# Sheet1.net
KiCad netlist of a schematic drawn in Altium Designer
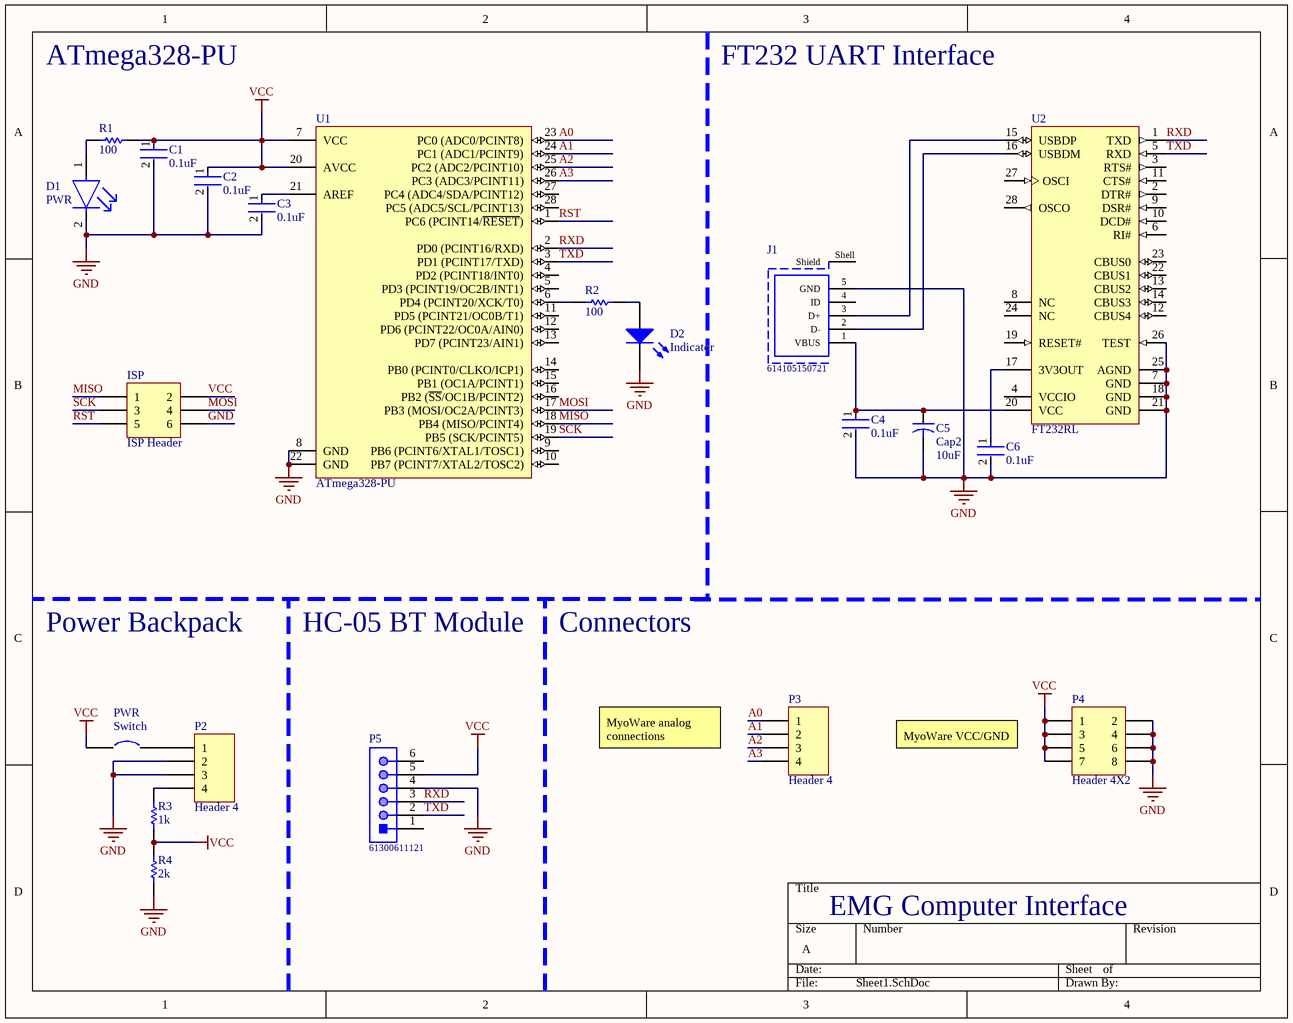
[diagram p0: Sheet1.SchDoc]

(export (version "E")
  (design (tool "Eeschema 10.0.6"))
  (components
    (comp (ref "C1")
      (value "0.1uF")
      (footprint "FP-1206-L_3_2_0_2-W_1_6_0-IPC_C")
      (description "General Purpose Ceramic Capacitor, 1206, 100nF, 5%, X7R, 15%, 100V")
      (fields (field (name "TOLERANCE") "5%") (field (name "VOLTAGE") "100V"))
      (libsource (lib "Altium Content Vault") (part "b4654b650e69147ec39a6b967a45e02"))
    )
    (comp (ref "C2")
      (value "0.1uF")
      (footprint "FP-1206-L_3_2_0_2-W_1_6_0-IPC_C")
      (description "General Purpose Ceramic Capacitor, 1206, 100nF, 5%, X7R, 15%, 100V")
      (fields (field (name "TOLERANCE") "5%") (field (name "VOLTAGE") "100V"))
      (libsource (lib "Altium Content Vault") (part "b4654b650e69147ec39a6b967a45e02"))
    )
    (comp (ref "C3")
      (value "0.1uF")
      (footprint "FP-1206-L_3_2_0_2-W_1_6_0-IPC_C")
      (description "General Purpose Ceramic Capacitor, 1206, 100nF, 5%, X7R, 15%, 100V")
      (fields (field (name "TOLERANCE") "5%") (field (name "VOLTAGE") "100V"))
      (libsource (lib "Altium Content Vault") (part "b4654b650e69147ec39a6b967a45e02"))
    )
    (comp (ref "C4")
      (value "0.1uF")
      (footprint "FP-1206-L_3_2_0_2-W_1_6_0-IPC_C")
      (description "General Purpose Ceramic Capacitor, 1206, 100nF, 5%, X7R, 15%, 100V")
      (fields (field (name "TOLERANCE") "5%") (field (name "VOLTAGE") "100V"))
      (libsource (lib "Altium Content Vault") (part "b4654b650e69147ec39a6b967a45e02"))
    )
    (comp (ref "C5")
      (value "Cap2")
      (footprint "CAPR5-4X5")
      (description "Capacitor")
      (fields (field (name "ALTIUM_VALUE") "10uF") (field (name "PUBLISHER") "Altium Limited"))
      (libsource (lib "Miscellaneous Devices") (part "Cap2"))
    )
    (comp (ref "C6")
      (value "0.1uF")
      (footprint "FP-1206-L_3_2_0_2-W_1_6_0-IPC_C")
      (description "General Purpose Ceramic Capacitor, 1206, 100nF, 5%, X7R, 15%, 100V")
      (fields (field (name "TOLERANCE") "5%") (field (name "VOLTAGE") "100V"))
      (libsource (lib "Altium Content Vault") (part "b4654b650e69147ec39a6b967a45e02"))
    )
    (comp (ref "D1")
      (value "PWR")
      (footprint "FP-SML-LX1206GC-TR-MFG")
      (description "LED GREEN CLEAR 1206 SMD")
      (libsource (lib "Altium Content Vault") (part "ab1c01a81903e929fc6c44469aada92"))
    )
    (comp (ref "D2")
      (value "Indicator")
      (footprint "1206_A")
      (description "SMD mono-color Chip LED, WL-SMCW, Super Red")
      (fields (field (name "MANUFACTURER") "Wuerth Elektronik") (field (name "PARTNUMBER") "150120SS75000"))
      (libsource (lib "Altium Content Vault") (part "WE-LED_K1A2-2"))
    )
    (comp (ref "ISP")
      (value "ISP Header")
      (footprint "HDR2X3")
      (description "Header, 3-Pin, Dual row")
      (fields (field (name "PUBLISHER") "Altium Limited"))
      (libsource (lib "Miscellaneous Connectors") (part "Header 3X2"))
    )
    (comp (ref "J1")
      (value "614105150721")
      (footprint "614105150721")
      (description "Micro USB 2.0 Type B Receptacle WR-COM, Vertical, THT")
      (fields (field (name "MANUFACTURER") "Wurth Elektronik") (field (name "PUBLISHER") "WurthElektronik"))
      (libsource (lib "Altium Content Vault") (part "WE-USB-5-1SHLD"))
    )
    (comp (ref "P2")
      (value "Header 4")
      (footprint "HDR1X4")
      (description "Header, 4-Pin")
      (fields (field (name "PUBLISHER") "Altium Limited"))
      (libsource (lib "Miscellaneous Connectors") (part "Header 4"))
    )
    (comp (ref "P3")
      (value "Header 4")
      (footprint "HDR1X4")
      (description "Header, 4-Pin")
      (fields (field (name "PUBLISHER") "Altium Limited"))
      (libsource (lib "Miscellaneous Connectors") (part "Header 4"))
    )
    (comp (ref "P4")
      (value "Header 4X2")
      (footprint "HDR2X4")
      (description "Header, 4-Pin, Dual row")
      (fields (field (name "PUBLISHER") "Altium Limited"))
      (libsource (lib "Miscellaneous Connectors") (part "Header 4X2"))
    )
    (comp (ref "P5")
      (value "61300611121")
      (footprint "61300611121")
      (description "THT Vertical Pin Header WR-PHD, Pitch 2.54 mm, Single Row, 6 pins")
      (fields (field (name "MANUFACTURER") "Wurth Elektronik") (field (name "PUBLISHER") "WurthElektronik"))
      (libsource (lib "Altium Content Vault") (part "WE-CN-1P-M-R6"))
    )
    (comp (ref "PWR")
      (value "Switch")
      (footprint "SPST-2")
      (description "Circuit Breaker")
      (fields (field (name "PUBLISHER") "Altium Limited"))
      (libsource (lib "Miscellaneous Devices") (part "Circuit Breaker"))
    )
    (comp (ref "R1")
      (value "100")
      (footprint "RESC3216X70X50NL05T20")
      (fields (field (name "MANUFACTURER") "Panasonic") (field (name "PART NUMBER") "ERJ-8ENF1000V"))
      (libsource (lib "Altium Content Vault") (part "RES"))
    )
    (comp (ref "R2")
      (value "100")
      (footprint "RESC3216X70X50NL05T20")
      (fields (field (name "MANUFACTURER") "Panasonic") (field (name "PART NUMBER") "ERJ-8ENF1000V"))
      (libsource (lib "Altium Content Vault") (part "RES"))
    )
    (comp (ref "R3")
      (value "1k")
      (footprint "RESC3216X70X50LL05T20")
      (fields (field (name "MANUFACTURER") "Panasonic") (field (name "PART NUMBER") "ERJ-8ENF1001V"))
      (libsource (lib "Altium Content Vault") (part "RES"))
    )
    (comp (ref "R4")
      (value "2k")
      (footprint "RESC3216X70X50NL05T20")
      (fields (field (name "PART NUMBER") "ERJ-8ENF2001V") (field (name "MANUFACTURER") "Panasonic"))
      (libsource (lib "Altium Content Vault") (part "RES"))
    )
    (comp (ref "U1")
      (value "ATmega328-PU")
      (footprint "28P3")
      (libsource (lib "Altium Content Vault") (part "MC-8B-ATM48-IL28"))
    )
    (comp (ref "U2")
      (value "FT232RL")
      (footprint "FTDI-SSOP-28_M")
      (description "IC USB FS SERIAL UART 28-SSOP")
      (fields (field (name "MANUFACTURER") "FTDI"))
      (libsource (lib "Altium Content Vault") (part "FTDI-FT232-SSOP-28"))
    )
  )
  (nets
    (net (code "1") (name "/A0") (class "Default")
      (node (ref "P3") (pin "1") (pinfunction "1_1") (pintype "passive"))
      (node (ref "U1") (pin "23") (pinfunction "PC0_(ADC0/PCINT8)_23") (pintype "bidirectional"))
    )
    (net (code "2") (name "/A1") (class "Default")
      (node (ref "P3") (pin "2") (pinfunction "2_2") (pintype "passive"))
      (node (ref "U1") (pin "24") (pinfunction "PC1_(ADC1/PCINT9)_24") (pintype "bidirectional"))
    )
    (net (code "3") (name "/A2") (class "Default")
      (node (ref "P3") (pin "3") (pinfunction "3_3") (pintype "passive"))
      (node (ref "U1") (pin "25") (pinfunction "PC2_(ADC2/PCINT10)_25") (pintype "bidirectional"))
    )
    (net (code "4") (name "/A3") (class "Default")
      (node (ref "P3") (pin "4") (pinfunction "4_4") (pintype "passive"))
      (node (ref "U1") (pin "26") (pinfunction "PC3_(ADC3/PCINT11)_26") (pintype "bidirectional"))
    )
    (net (code "5") (name "/MISO") (class "Default")
      (node (ref "ISP") (pin "1") (pinfunction "1_1") (pintype "passive"))
      (node (ref "U1") (pin "18") (pinfunction "PB4_(MISO/PCINT4)_18") (pintype "bidirectional"))
    )
    (net (code "6") (name "/MOSI") (class "Default")
      (node (ref "ISP") (pin "4") (pinfunction "4_4") (pintype "passive"))
      (node (ref "U1") (pin "17") (pinfunction "PB3_(MOSI/OC2A/PCINT3)_17") (pintype "bidirectional"))
    )
    (net (code "7") (name "/RST") (class "Default")
      (node (ref "ISP") (pin "5") (pinfunction "5_5") (pintype "passive"))
      (node (ref "U1") (pin "1") (pinfunction "PC6_(PCINT14/~{RESET})_1") (pintype "bidirectional"))
    )
    (net (code "8") (name "/RXD") (class "Default")
      (node (ref "P5") (pin "3") (pinfunction "3_3") (pintype "passive"))
      (node (ref "U1") (pin "2") (pinfunction "PD0_(PCINT16/RXD)_2") (pintype "bidirectional"))
      (node (ref "U2") (pin "1") (pinfunction "TXD_1") (pintype "output"))
    )
    (net (code "9") (name "/SCK") (class "Default")
      (node (ref "ISP") (pin "3") (pinfunction "3_3") (pintype "passive"))
      (node (ref "U1") (pin "19") (pinfunction "PB5_(SCK/PCINT5)_19") (pintype "bidirectional"))
    )
    (net (code "10") (name "/TXD") (class "Default")
      (node (ref "P5") (pin "2") (pinfunction "2_2") (pintype "passive"))
      (node (ref "U1") (pin "3") (pinfunction "PD1_(PCINT17/TXD)_3") (pintype "bidirectional"))
      (node (ref "U2") (pin "5") (pinfunction "RXD_5") (pintype "input"))
    )
    (net (code "11") (name "GND") (class "Default")
      (node (ref "C1") (pin "2") (pinfunction "2_2") (pintype "passive"))
      (node (ref "C2") (pin "2") (pinfunction "2_2") (pintype "passive"))
      (node (ref "C3") (pin "2") (pinfunction "2_2") (pintype "passive"))
      (node (ref "C4") (pin "2") (pinfunction "2_2") (pintype "passive"))
      (node (ref "C5") (pin "2") (pinfunction "2_2") (pintype "passive"))
      (node (ref "C6") (pin "2") (pinfunction "2_2") (pintype "passive"))
      (node (ref "D1") (pin "2") (pinfunction "C_2") (pintype "passive"))
      (node (ref "D2") (pin "1") (pinfunction "K_1") (pintype "passive"))
      (node (ref "ISP") (pin "6") (pinfunction "6_6") (pintype "passive"))
      (node (ref "J1") (pin "5") (pinfunction "GND_5") (pintype "passive"))
      (node (ref "P2") (pin "2") (pinfunction "2_2") (pintype "passive"))
      (node (ref "P2") (pin "3") (pinfunction "3_3") (pintype "passive"))
      (node (ref "P4") (pin "2") (pinfunction "2_2") (pintype "passive"))
      (node (ref "P4") (pin "4") (pinfunction "4_4") (pintype "passive"))
      (node (ref "P4") (pin "6") (pinfunction "6_6") (pintype "passive"))
      (node (ref "P4") (pin "8") (pinfunction "8_8") (pintype "passive"))
      (node (ref "P5") (pin "4") (pinfunction "4_4") (pintype "passive"))
      (node (ref "R4") (pin "1") (pinfunction "1_1") (pintype "passive"))
      (node (ref "U1") (pin "22") (pinfunction "GND_22") (pintype "power_in"))
      (node (ref "U1") (pin "8") (pinfunction "GND_8") (pintype "power_in"))
      (node (ref "U2") (pin "18") (pinfunction "GND_18") (pintype "power_in"))
      (node (ref "U2") (pin "21") (pinfunction "GND_21") (pintype "power_in"))
      (node (ref "U2") (pin "25") (pinfunction "AGND_25") (pintype "power_in"))
      (node (ref "U2") (pin "26") (pinfunction "TEST_26") (pintype "input"))
      (node (ref "U2") (pin "7") (pinfunction "GND_7") (pintype "power_in"))
    )
    (net (code "12") (name "Net-(D1-A)") (class "Default")
      (node (ref "D1") (pin "1") (pinfunction "A_1") (pintype "passive"))
      (node (ref "R1") (pin "1") (pinfunction "1_1") (pintype "passive"))
    )
    (net (code "13") (name "Net-(D2-A)") (class "Default")
      (node (ref "D2") (pin "2") (pinfunction "A_2") (pintype "passive"))
      (node (ref "R2") (pin "2") (pinfunction "2_2") (pintype "passive"))
    )
    (net (code "14") (name "Net-(J1-D+)") (class "Default")
      (node (ref "J1") (pin "3") (pinfunction "D+_3") (pintype "passive"))
      (node (ref "U2") (pin "15") (pinfunction "USBDP_15") (pintype "bidirectional"))
    )
    (net (code "15") (name "Net-(J1-D-)") (class "Default")
      (node (ref "J1") (pin "2") (pinfunction "D-_2") (pintype "passive"))
      (node (ref "U2") (pin "16") (pinfunction "USBDM_16") (pintype "bidirectional"))
    )
    (net (code "16") (name "Net-(J1-VBUS)") (class "Default")
      (node (ref "C4") (pin "1") (pinfunction "1_1") (pintype "passive"))
      (node (ref "C5") (pin "1") (pinfunction "1_1") (pintype "passive"))
      (node (ref "J1") (pin "1") (pinfunction "VBUS_1") (pintype "passive"))
      (node (ref "U2") (pin "20") (pinfunction "VCC_20") (pintype "power_in"))
    )
    (net (code "17") (name "Net-(P2-Pad1)") (class "Default")
      (node (ref "P2") (pin "1") (pinfunction "1_1") (pintype "passive"))
      (node (ref "PWR") (pin "2") (pinfunction "2_2") (pintype "passive"))
    )
    (net (code "18") (name "Net-(P2-Pad4)") (class "Default")
      (node (ref "P2") (pin "4") (pinfunction "4_4") (pintype "passive"))
      (node (ref "R3") (pin "2") (pinfunction "2_2") (pintype "passive"))
    )
    (net (code "19") (name "Net-(U1-AREF)") (class "Default")
      (node (ref "C3") (pin "1") (pinfunction "1_1") (pintype "passive"))
      (node (ref "U1") (pin "21") (pinfunction "AREF_21") (pintype "power_in"))
    )
    (net (code "20") (name "Net-(U1-PD4_(PCINT20{slash}XCK{slash}T0))") (class "Default")
      (node (ref "R2") (pin "1") (pinfunction "1_1") (pintype "passive"))
      (node (ref "U1") (pin "6") (pinfunction "PD4_(PCINT20/XCK/T0)_6") (pintype "bidirectional"))
    )
    (net (code "21") (name "Net-(U2-3V3OUT)") (class "Default")
      (node (ref "C6") (pin "1") (pinfunction "1_1") (pintype "passive"))
      (node (ref "U2") (pin "17") (pinfunction "3V3OUT_17") (pintype "power_in"))
    )
    (net (code "22") (name "VCC") (class "Default")
      (node (ref "C1") (pin "1") (pinfunction "1_1") (pintype "passive"))
      (node (ref "C2") (pin "1") (pinfunction "1_1") (pintype "passive"))
      (node (ref "ISP") (pin "2") (pinfunction "2_2") (pintype "passive"))
      (node (ref "P4") (pin "1") (pinfunction "1_1") (pintype "passive"))
      (node (ref "P4") (pin "3") (pinfunction "3_3") (pintype "passive"))
      (node (ref "P4") (pin "5") (pinfunction "5_5") (pintype "passive"))
      (node (ref "P4") (pin "7") (pinfunction "7_7") (pintype "passive"))
      (node (ref "P5") (pin "5") (pinfunction "5_5") (pintype "passive"))
      (node (ref "PWR") (pin "1") (pinfunction "1_1") (pintype "passive"))
      (node (ref "R1") (pin "2") (pinfunction "2_2") (pintype "passive"))
      (node (ref "R3") (pin "1") (pinfunction "1_1") (pintype "passive"))
      (node (ref "R4") (pin "2") (pinfunction "2_2") (pintype "passive"))
      (node (ref "U1") (pin "20") (pinfunction "AVCC_20") (pintype "power_in"))
      (node (ref "U1") (pin "7") (pinfunction "VCC_7") (pintype "power_in"))
    )
    (net (code "23") (name "unconnected-(J1-ID-Pad4)") (class "Default")
      (node (ref "J1") (pin "4") (pinfunction "ID_4") (pintype "passive"))
    )
    (net (code "24") (name "unconnected-(J1-Shield-PadShell)") (class "Default")
      (node (ref "J1") (pin "Shell") (pinfunction "Shield_Shell") (pintype "passive"))
    )
    (net (code "25") (name "unconnected-(P5-Pad1)") (class "Default")
      (node (ref "P5") (pin "1") (pinfunction "1_1") (pintype "passive"))
    )
    (net (code "26") (name "unconnected-(P5-Pad6)") (class "Default")
      (node (ref "P5") (pin "6") (pinfunction "6_6") (pintype "passive"))
    )
    (net (code "27") (name "unconnected-(U1-PB0_(PCINT0{slash}CLKO{slash}ICP1)-Pad14)") (class "Default")
      (node (ref "U1") (pin "14") (pinfunction "PB0_(PCINT0/CLKO/ICP1)_14") (pintype "bidirectional"))
    )
    (net (code "28") (name "unconnected-(U1-PB1_(OC1A{slash}PCINT1)-Pad15)") (class "Default")
      (node (ref "U1") (pin "15") (pinfunction "PB1_(OC1A/PCINT1)_15") (pintype "bidirectional"))
    )
    (net (code "29") (name "unconnected-(U1-PB2_(~{SS}{slash}OC1B{slash}PCINT2)-Pad16)") (class "Default")
      (node (ref "U1") (pin "16") (pinfunction "PB2_(~{SS}/OC1B/PCINT2)_16") (pintype "bidirectional"))
    )
    (net (code "30") (name "unconnected-(U1-PB6_(PCINT6{slash}XTAL1{slash}TOSC1)-Pad9)") (class "Default")
      (node (ref "U1") (pin "9") (pinfunction "PB6_(PCINT6/XTAL1/TOSC1)_9") (pintype "bidirectional"))
    )
    (net (code "31") (name "unconnected-(U1-PB7_(PCINT7{slash}XTAL2{slash}TOSC2)-Pad10)") (class "Default")
      (node (ref "U1") (pin "10") (pinfunction "PB7_(PCINT7/XTAL2/TOSC2)_10") (pintype "bidirectional"))
    )
    (net (code "32") (name "unconnected-(U1-PC4_(ADC4{slash}SDA{slash}PCINT12)-Pad27)") (class "Default")
      (node (ref "U1") (pin "27") (pinfunction "PC4_(ADC4/SDA/PCINT12)_27") (pintype "bidirectional"))
    )
    (net (code "33") (name "unconnected-(U1-PC5_(ADC5{slash}SCL{slash}PCINT13)-Pad28)") (class "Default")
      (node (ref "U1") (pin "28") (pinfunction "PC5_(ADC5/SCL/PCINT13)_28") (pintype "bidirectional"))
    )
    (net (code "34") (name "unconnected-(U1-PD2_(PCINT18{slash}INT0)-Pad4)") (class "Default")
      (node (ref "U1") (pin "4") (pinfunction "PD2_(PCINT18/INT0)_4") (pintype "bidirectional"))
    )
    (net (code "35") (name "unconnected-(U1-PD3_(PCINT19{slash}OC2B{slash}INT1)-Pad5)") (class "Default")
      (node (ref "U1") (pin "5") (pinfunction "PD3_(PCINT19/OC2B/INT1)_5") (pintype "bidirectional"))
    )
    (net (code "36") (name "unconnected-(U1-PD5_(PCINT21{slash}OC0B{slash}T1)-Pad11)") (class "Default")
      (node (ref "U1") (pin "11") (pinfunction "PD5_(PCINT21/OC0B/T1)_11") (pintype "bidirectional"))
    )
    (net (code "37") (name "unconnected-(U1-PD6_(PCINT22{slash}OC0A{slash}AIN0)-Pad12)") (class "Default")
      (node (ref "U1") (pin "12") (pinfunction "PD6_(PCINT22/OC0A/AIN0)_12") (pintype "bidirectional"))
    )
    (net (code "38") (name "unconnected-(U1-PD7_(PCINT23{slash}AIN1)-Pad13)") (class "Default")
      (node (ref "U1") (pin "13") (pinfunction "PD7_(PCINT23/AIN1)_13") (pintype "bidirectional"))
    )
    (net (code "39") (name "unconnected-(U2-CBUS0-Pad23)") (class "Default")
      (node (ref "U2") (pin "23") (pinfunction "CBUS0_23") (pintype "bidirectional"))
    )
    (net (code "40") (name "unconnected-(U2-CBUS1-Pad22)") (class "Default")
      (node (ref "U2") (pin "22") (pinfunction "CBUS1_22") (pintype "bidirectional"))
    )
    (net (code "41") (name "unconnected-(U2-CBUS2-Pad13)") (class "Default")
      (node (ref "U2") (pin "13") (pinfunction "CBUS2_13") (pintype "bidirectional"))
    )
    (net (code "42") (name "unconnected-(U2-CBUS3-Pad14)") (class "Default")
      (node (ref "U2") (pin "14") (pinfunction "CBUS3_14") (pintype "bidirectional"))
    )
    (net (code "43") (name "unconnected-(U2-CBUS4-Pad12)") (class "Default")
      (node (ref "U2") (pin "12") (pinfunction "CBUS4_12") (pintype "bidirectional"))
    )
    (net (code "44") (name "unconnected-(U2-CTS#-Pad11)") (class "Default")
      (node (ref "U2") (pin "11") (pinfunction "CTS#_11") (pintype "input"))
    )
    (net (code "45") (name "unconnected-(U2-DCD#-Pad10)") (class "Default")
      (node (ref "U2") (pin "10") (pinfunction "DCD#_10") (pintype "input"))
    )
    (net (code "46") (name "unconnected-(U2-DSR#-Pad9)") (class "Default")
      (node (ref "U2") (pin "9") (pinfunction "DSR#_9") (pintype "input"))
    )
    (net (code "47") (name "unconnected-(U2-DTR#-Pad2)") (class "Default")
      (node (ref "U2") (pin "2") (pinfunction "DTR#_2") (pintype "output"))
    )
    (net (code "48") (name "unconnected-(U2-NC-Pad8)") (class "Default")
      (node (ref "U2") (pin "8") (pinfunction "NC_8") (pintype "passive"))
    )
    (net (code "49") (name "unconnected-(U2-NC-Pad24)") (class "Default")
      (node (ref "U2") (pin "24") (pinfunction "NC_24") (pintype "passive"))
    )
    (net (code "50") (name "unconnected-(U2-OSCI-Pad27)") (class "Default")
      (node (ref "U2") (pin "27") (pinfunction "OSCI_27") (pintype "input"))
    )
    (net (code "51") (name "unconnected-(U2-OSCO-Pad28)") (class "Default")
      (node (ref "U2") (pin "28") (pinfunction "OSCO_28") (pintype "output"))
    )
    (net (code "52") (name "unconnected-(U2-RESET#-Pad19)") (class "Default")
      (node (ref "U2") (pin "19") (pinfunction "RESET#_19") (pintype "input"))
    )
    (net (code "53") (name "unconnected-(U2-RI#-Pad6)") (class "Default")
      (node (ref "U2") (pin "6") (pinfunction "RI#_6") (pintype "input"))
    )
    (net (code "54") (name "unconnected-(U2-RTS#-Pad3)") (class "Default")
      (node (ref "U2") (pin "3") (pinfunction "RTS#_3") (pintype "output"))
    )
    (net (code "55") (name "unconnected-(U2-VCCIO-Pad4)") (class "Default")
      (node (ref "U2") (pin "4") (pinfunction "VCCIO_4") (pintype "power_in"))
    )
  )
)
